# Reset.net
KiCad netlist of a schematic drawn in Altium Designer
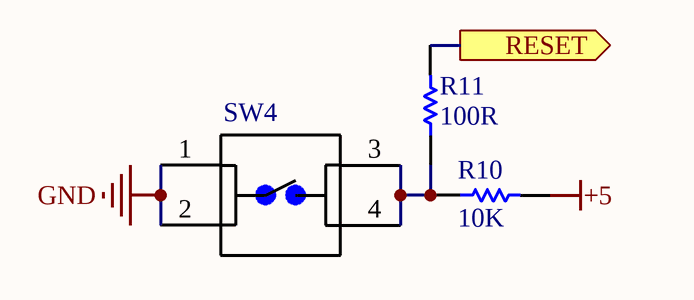
[diagram p0: Reset.SchDoc]

(export (version "E")
  (design (tool "Eeschema 10.0.6"))
  (components
    (comp (ref "R10")
      (value "10K")
      (footprint "RESC0805(2012)_L")
      (description "10K2 0.125W 1% 0805 (2012 Metric)  SMD")
      (fields (field (name "TOLERANCE") "1 %") (field (name "POWER") "0.125 W"))
      (libsource (lib "Altium Content Vault") (part "RES"))
    )
    (comp (ref "R11")
      (value "100R")
      (footprint "RESC0805(2012)_L")
      (description "100R 0.125W 1% 0805 (2012 Metric)  SMD")
      (fields (field (name "POWER") "0.125 W") (field (name "TOLERANCE") "1 %"))
      (libsource (lib "Altium Content Vault") (part "RES"))
    )
    (comp (ref "SW4")
      (value "1825910-7")
      (footprint "Switch 6mm 24V (NO)")
      (description "FSM4JAH=6MM TACT SWITCH, HIGH TEMP")
      (fields (field (name "MF") "TE Connectivity") (field (name "DIGI-KEY_PART_NUMBER") "450-1804-ND"))
      (libsource (lib "Husky Robotics Standard Library 2019-2020") (part "Switch 6mm 24V (NO)"))
    )
  )
  (nets
    (net (code "1") (name "+5") (class "Default")
      (node (ref "R10") (pin "2") (pinfunction "2_2") (pintype "passive"))
    )
    (net (code "2") (name "/RESET") (class "Default")
      (node (ref "R11") (pin "2") (pinfunction "2_2") (pintype "passive"))
    )
    (net (code "3") (name "GND") (class "Default")
      (node (ref "SW4") (pin "1") (pinfunction "1_1") (pintype "passive"))
      (node (ref "SW4") (pin "2") (pinfunction "2_2") (pintype "passive"))
    )
    (net (code "4") (name "Net-(R10-Pad1)") (class "Default")
      (node (ref "R10") (pin "1") (pinfunction "1_1") (pintype "passive"))
      (node (ref "R11") (pin "1") (pinfunction "1_1") (pintype "passive"))
      (node (ref "SW4") (pin "3") (pinfunction "3_3") (pintype "passive"))
      (node (ref "SW4") (pin "4") (pinfunction "4_4") (pintype "passive"))
    )
  )
)
